# Sheet1.net
KiCad netlist of a schematic drawn in Altium Designer
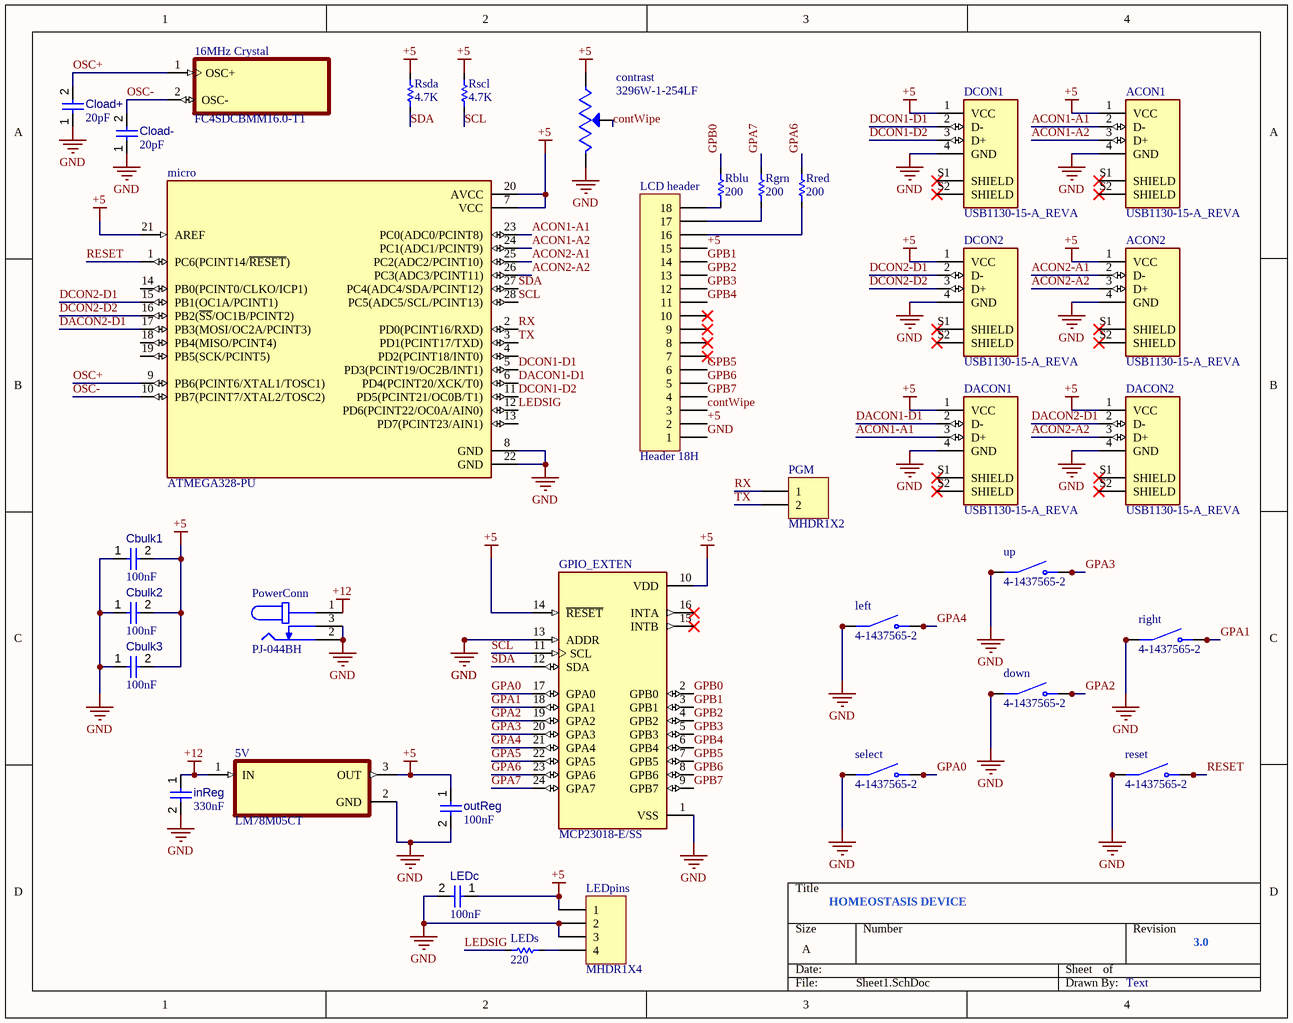
[diagram p0: Sheet1.SchDoc]

(export (version "E")
  (design (tool "Eeschema 10.0.6"))
  (components
    (comp (ref "5V")
      (value "LM78M05CT")
      (footprint "TO254P1054X470X1955-3")
      (description "Linear Voltage Regulator IC 1 Output 500mA TO-220-3")
      (fields (field (name "MF") "ON Semiconductor"))
      (libsource (lib "LM78M05CT") (part "LM78M05CT"))
    )
    (comp (ref "16MHz Crystal")
      (value "FC4SDCBMM16.0-T1")
      (footprint "XTAL_FOXSDLF/160-20")
      (description "16 MHz Â±30ppm Crystal 20pF 40 Ohms HC-49/US")
      (fields (field (name "MF") "Fox Electronics"))
      (libsource (lib "FC4SDCBMM16.0-T1") (part "FC4SDCBMM16.0-T1"))
    )
    (comp (ref "ACON1")
      (value "USB1130-15-A_REVA")
      (footprint "GCT_USB1130-15-A_REVA")
      (fields (field (name "MF") "{'manufacturer': u'Global Connector Technology'}"))
      (libsource (lib "SnapEDA_Library") (part "USB1130-15-A_REVA"))
    )
    (comp (ref "ACON2")
      (value "USB1130-15-A_REVA")
      (footprint "GCT_USB1130-15-A_REVA")
      (fields (field (name "MF") "{'manufacturer': u'Global Connector Technology'}"))
      (libsource (lib "SnapEDA_Library") (part "USB1130-15-A_REVA"))
    )
    (comp (ref "Cbulk1")
      (value "100nF")
      (footprint "CAPC0805(2012)145_L")
      (description "Chip Capacitor, 4.7µF +/-40%, 25V, 0805, Thickness 1.45 mm")
      (fields (field (name "TOLERANCE") "20%") (field (name "Comment") "Capacitor 4.7µF +/-40% 25V 0805"))
      (libsource (lib "University of Minnesota - Solar Vehicle Project") (part "CAP-NP-2"))
    )
    (comp (ref "Cbulk2")
      (value "100nF")
      (footprint "CAPC0805(2012)145_L")
      (description "Chip Capacitor, 4.7µF +/-40%, 25V, 0805, Thickness 1.45 mm")
      (fields (field (name "TOLERANCE") "20%") (field (name "Comment") "Capacitor 4.7µF +/-40% 25V 0805"))
      (libsource (lib "University of Minnesota - Solar Vehicle Project") (part "CAP-NP-2"))
    )
    (comp (ref "Cbulk3")
      (value "100nF")
      (footprint "CAPC0805(2012)145_L")
      (description "Chip Capacitor, 4.7µF +/-40%, 25V, 0805, Thickness 1.45 mm")
      (fields (field (name "TOLERANCE") "20%") (field (name "Comment") "Capacitor 4.7µF +/-40% 25V 0805"))
      (libsource (lib "University of Minnesota - Solar Vehicle Project") (part "CAP-NP-2"))
    )
    (comp (ref "Cload+")
      (value "20pF")
      (footprint "CAPC2013X135X45ML10T25")
      (description "Chip Capacitor, 1 uF, +/- 10%, 50 V, 0805 (2012 Metric)")
      (fields (field (name "TOLERANCE") "10%") (field (name "Comment") "Capacitor 1 uF +/- 10% 50 V 0805"))
      (libsource (lib "University of Minnesota - Solar Vehicle Project") (part "CAP-NP-2"))
    )
    (comp (ref "Cload-")
      (value "20pF")
      (footprint "CAPC2013X135X45ML10T25")
      (description "Chip Capacitor, 1 uF, +/- 10%, 50 V, 0805 (2012 Metric)")
      (fields (field (name "TOLERANCE") "10%") (field (name "Comment") "Capacitor 1 uF +/- 10% 50 V 0805"))
      (libsource (lib "University of Minnesota - Solar Vehicle Project") (part "CAP-NP-2"))
    )
    (comp (ref "contrast")
      (value "3296W-1-254LF")
      (footprint "TRIM_3296W-1-254LF")
      (fields (field (name "MF") "{'manufacturer': u'Bourns'}"))
      (libsource (lib "SnapEDA_Library") (part "3296W-1-254LF"))
    )
    (comp (ref "DACON1")
      (value "USB1130-15-A_REVA")
      (footprint "GCT_USB1130-15-A_REVA")
      (fields (field (name "MF") "{'manufacturer': u'Global Connector Technology'}"))
      (libsource (lib "SnapEDA_Library") (part "USB1130-15-A_REVA"))
    )
    (comp (ref "DACON2")
      (value "USB1130-15-A_REVA")
      (footprint "GCT_USB1130-15-A_REVA")
      (fields (field (name "MF") "{'manufacturer': u'Global Connector Technology'}"))
      (libsource (lib "SnapEDA_Library") (part "USB1130-15-A_REVA"))
    )
    (comp (ref "DCON1")
      (value "USB1130-15-A_REVA")
      (footprint "GCT_USB1130-15-A_REVA")
      (fields (field (name "MF") "{'manufacturer': u'Global Connector Technology'}"))
      (libsource (lib "SnapEDA_Library") (part "USB1130-15-A_REVA"))
    )
    (comp (ref "DCON2")
      (value "USB1130-15-A_REVA")
      (footprint "GCT_USB1130-15-A_REVA")
      (fields (field (name "MF") "{'manufacturer': u'Global Connector Technology'}"))
      (libsource (lib "SnapEDA_Library") (part "USB1130-15-A_REVA"))
    )
    (comp (ref "down")
      (value "4-1437565-2")
      (footprint "SW_4-1437565-2")
      (fields (field (name "MF") "{'manufacturer': u'TE Connectivity'}"))
      (libsource (lib "SnapEDA_Library") (part "4-1437565-2"))
    )
    (comp (ref "GPIO_EXTEN")
      (value "MCP23018-E/SS")
      (footprint "SOP65P780X200-24N")
      (description "IC: expander; 16bit I/O port; I2C; SSOP24; 1.8Ã·5.5VDC")
      (fields (field (name "MF") "{'manufacturer': u'Microchip'}"))
      (libsource (lib "SnapEDA_Library") (part "MCP23018-E/SS"))
    )
    (comp (ref "inReg")
      (value "330nF")
      (footprint "CAPC0805(2012)145_L")
      (description "Chip Capacitor, 4.7µF +/-40%, 25V, 0805, Thickness 1.45 mm")
      (fields (field (name "TOLERANCE") "20%") (field (name "Comment") "Capacitor 4.7µF +/-40% 25V 0805"))
      (libsource (lib "University of Minnesota - Solar Vehicle Project") (part "CAP-NP-2"))
    )
    (comp (ref "LCD header")
      (value "Header 18H")
      (footprint "HDR1X18H")
      (description "Header, 18-Pin, Right Angle")
      (fields (field (name "PUBLISHER") "Altium Limited"))
      (libsource (lib "Miscellaneous Connectors") (part "Header 18H"))
    )
    (comp (ref "LEDc")
      (value "100nF")
      (footprint "CAPC0805(2012)145_L")
      (description "Chip Capacitor, 4.7µF +/-40%, 25V, 0805, Thickness 1.45 mm")
      (fields (field (name "TOLERANCE") "20%") (field (name "Comment") "Capacitor 4.7µF +/-40% 25V 0805"))
      (libsource (lib "University of Minnesota - Solar Vehicle Project") (part "CAP-NP-2"))
    )
    (comp (ref "LEDpins")
      (value "MHDR1X4")
      (footprint "MHDR1X4")
      (description "Header, 4-Pin")
      (fields (field (name "PUBLISHER") "Altium Limited"))
      (libsource (lib "Miscellaneous Connectors") (part "MHDR1X4"))
    )
    (comp (ref "LEDs")
      (value "220")
      (footprint "0805_Resistor")
      (description "RES 4.7K OHM 1/8W 1% 0805 SMD")
      (fields
        (field (name "MANUFACTURER") "Yageo")
        (field (name "MANUFACTURER PART NUMBER") "AC0805FR-074K7L")
        (field (name "SVP CREATOR") "Andrew Wu")
      )
      (libsource (lib "University of Minnesota - Solar Vehicle Project") (part "Symbol"))
    )
    (comp (ref "left")
      (value "4-1437565-2")
      (footprint "SW_4-1437565-2")
      (fields (field (name "MF") "{'manufacturer': u'TE Connectivity'}"))
      (libsource (lib "SnapEDA_Library") (part "4-1437565-2"))
    )
    (comp (ref "micro")
      (value "ATMEGA328-PU")
      (footprint "DIP787W46P254L3467H508Q28")
      (description "AVR AVRÂ® ATmega Microcontroller IC 8-Bit 20MHz 32KB (16K x 16) FLASH 28-PDIP")
      (fields (field (name "MF") "{'manufacturer': u'Microchip Technology'}"))
      (libsource (lib "SnapEDA_Library") (part "ATMEGA328-PU"))
    )
    (comp (ref "outReg")
      (value "100nF")
      (footprint "CAPC0805(2012)145_L")
      (description "Chip Capacitor, 4.7µF +/-40%, 25V, 0805, Thickness 1.45 mm")
      (fields (field (name "TOLERANCE") "20%") (field (name "Comment") "Capacitor 4.7µF +/-40% 25V 0805"))
      (libsource (lib "University of Minnesota - Solar Vehicle Project") (part "CAP-NP-2"))
    )
    (comp (ref "PGM")
      (value "MHDR1X2")
      (footprint "MHDR1X2")
      (description "Header, 2-Pin")
      (fields (field (name "PUBLISHER") "Altium Limited"))
      (libsource (lib "Miscellaneous Connectors") (part "MHDR1X2"))
    )
    (comp (ref "PowerConn")
      (value "PJ-044BH")
      (footprint "CUI_PJ-044BH")
      (description "2.5 mm Center Pin, 5.0 A, Vertical, Through Hole, Dc Power Jack Connector")
      (fields (field (name "MF") "{'manufacturer': u'CUI Devices'}"))
      (libsource (lib "SnapEDA_Library") (part "PJ-044BH"))
    )
    (comp (ref "Rblu")
      (value "200")
      (footprint "0805_Resistor")
      (description "RES 200 OHM 1/8W 1% 0805 SMD")
      (fields
        (field (name "MANUFACTURER") "Yageo")
        (field (name "MANUFACTURER PART NUMBER") "RC0805FR-07200RL")
        (field (name "SVP CREATOR") "Spencer Berglund")
      )
      (libsource (lib "University of Minnesota - Solar Vehicle Project") (part "Symbol"))
    )
    (comp (ref "reset")
      (value "4-1437565-2")
      (footprint "SW_4-1437565-2")
      (fields (field (name "MF") "{'manufacturer': u'TE Connectivity'}"))
      (libsource (lib "SnapEDA_Library") (part "4-1437565-2"))
    )
    (comp (ref "Rgrn")
      (value "200")
      (footprint "0805_Resistor")
      (description "RES 200 OHM 1/8W 1% 0805 SMD")
      (fields
        (field (name "MANUFACTURER") "Yageo")
        (field (name "MANUFACTURER PART NUMBER") "RC0805FR-07200RL")
        (field (name "SVP CREATOR") "Spencer Berglund")
      )
      (libsource (lib "University of Minnesota - Solar Vehicle Project") (part "Symbol"))
    )
    (comp (ref "right")
      (value "4-1437565-2")
      (footprint "SW_4-1437565-2")
      (fields (field (name "MF") "{'manufacturer': u'TE Connectivity'}"))
      (libsource (lib "SnapEDA_Library") (part "4-1437565-2"))
    )
    (comp (ref "Rred")
      (value "200")
      (footprint "0805_Resistor")
      (description "RES 200 OHM 1/8W 1% 0805 SMD")
      (fields
        (field (name "MANUFACTURER") "Yageo")
        (field (name "MANUFACTURER PART NUMBER") "RC0805FR-07200RL")
        (field (name "SVP CREATOR") "Spencer Berglund")
      )
      (libsource (lib "University of Minnesota - Solar Vehicle Project") (part "Symbol"))
    )
    (comp (ref "Rscl")
      (value "4.7K")
      (footprint "0805_Resistor")
      (description "RES 4.7K OHM 1/8W 1% 0805 SMD")
      (fields
        (field (name "MANUFACTURER") "Yageo")
        (field (name "MANUFACTURER PART NUMBER") "AC0805FR-074K7L")
        (field (name "SVP CREATOR") "Andrew Wu")
      )
      (libsource (lib "University of Minnesota - Solar Vehicle Project") (part "Symbol"))
    )
    (comp (ref "Rsda")
      (value "4.7K")
      (footprint "0805_Resistor")
      (description "RES 4.7K OHM 1/8W 1% 0805 SMD")
      (fields
        (field (name "MANUFACTURER") "Yageo")
        (field (name "MANUFACTURER PART NUMBER") "AC0805FR-074K7L")
        (field (name "SVP CREATOR") "Andrew Wu")
      )
      (libsource (lib "University of Minnesota - Solar Vehicle Project") (part "Symbol"))
    )
    (comp (ref "select")
      (value "4-1437565-2")
      (footprint "SW_4-1437565-2")
      (fields (field (name "MF") "{'manufacturer': u'TE Connectivity'}"))
      (libsource (lib "SnapEDA_Library") (part "4-1437565-2"))
    )
    (comp (ref "up")
      (value "4-1437565-2")
      (footprint "SW_4-1437565-2")
      (fields (field (name "MF") "{'manufacturer': u'TE Connectivity'}"))
      (libsource (lib "SnapEDA_Library") (part "4-1437565-2"))
    )
  )
  (nets
    (net (code "1") (name "+5") (class "Default")
      (node (ref "5V") (pin "3") (pinfunction "OUT_3") (pintype "output"))
      (node (ref "ACON1") (pin "1") (pinfunction "VCC_1") (pintype "power_in"))
      (node (ref "ACON2") (pin "1") (pinfunction "VCC_1") (pintype "power_in"))
      (node (ref "Cbulk1") (pin "2") (pinfunction "2_2") (pintype "passive"))
      (node (ref "Cbulk2") (pin "2") (pinfunction "2_2") (pintype "passive"))
      (node (ref "Cbulk3") (pin "2") (pinfunction "2_2") (pintype "passive"))
      (node (ref "DACON1") (pin "1") (pinfunction "VCC_1") (pintype "power_in"))
      (node (ref "DACON2") (pin "1") (pinfunction "VCC_1") (pintype "power_in"))
      (node (ref "DCON1") (pin "1") (pinfunction "VCC_1") (pintype "power_in"))
      (node (ref "DCON2") (pin "1") (pinfunction "VCC_1") (pintype "power_in"))
      (node (ref "GPIO_EXTEN") (pin "10") (pinfunction "VDD_10") (pintype "power_in"))
      (node (ref "GPIO_EXTEN") (pin "14") (pinfunction "~{RESET}_14") (pintype "input"))
      (node (ref "LCD header") (pin "15") (pinfunction "15_15") (pintype "passive"))
      (node (ref "LCD header") (pin "2") (pinfunction "2_2") (pintype "passive"))
      (node (ref "LEDc") (pin "1") (pinfunction "1_1") (pintype "passive"))
      (node (ref "LEDpins") (pin "1") (pinfunction "1_1") (pintype "passive"))
      (node (ref "Rscl") (pin "1") (pinfunction "1_1") (pintype "passive"))
      (node (ref "Rsda") (pin "1") (pinfunction "1_1") (pintype "passive"))
      (node (ref "contrast") (pin "1") (pinfunction "CCW_1") (pintype "passive"))
      (node (ref "micro") (pin "20") (pinfunction "AVCC_20") (pintype "power_in"))
      (node (ref "micro") (pin "21") (pinfunction "AREF_21") (pintype "input"))
      (node (ref "micro") (pin "7") (pinfunction "VCC_7") (pintype "power_in"))
      (node (ref "outReg") (pin "1") (pinfunction "1_1") (pintype "passive"))
    )
    (net (code "2") (name "+12") (class "Default")
      (node (ref "5V") (pin "1") (pinfunction "IN_1") (pintype "input"))
      (node (ref "PowerConn") (pin "1") (pinfunction "1_1") (pintype "passive"))
      (node (ref "inReg") (pin "1") (pinfunction "1_1") (pintype "passive"))
    )
    (net (code "3") (name "/ACON1-A1") (class "Default")
      (node (ref "ACON1") (pin "2") (pinfunction "D-_2") (pintype "bidirectional"))
      (node (ref "DACON1") (pin "3") (pinfunction "D+_3") (pintype "bidirectional"))
      (node (ref "micro") (pin "23") (pinfunction "PC0(ADC0/PCINT8)_23") (pintype "bidirectional"))
    )
    (net (code "4") (name "/ACON1-A2") (class "Default")
      (node (ref "ACON1") (pin "3") (pinfunction "D+_3") (pintype "bidirectional"))
      (node (ref "micro") (pin "24") (pinfunction "PC1(ADC1/PCINT9)_24") (pintype "bidirectional"))
    )
    (net (code "5") (name "/ACON2-A1") (class "Default")
      (node (ref "ACON2") (pin "2") (pinfunction "D-_2") (pintype "bidirectional"))
      (node (ref "micro") (pin "25") (pinfunction "PC2(ADC2/PCINT10)_25") (pintype "bidirectional"))
    )
    (net (code "6") (name "/ACON2-A2") (class "Default")
      (node (ref "ACON2") (pin "3") (pinfunction "D+_3") (pintype "bidirectional"))
      (node (ref "DACON2") (pin "3") (pinfunction "D+_3") (pintype "bidirectional"))
      (node (ref "micro") (pin "26") (pinfunction "PC3(ADC3/PCINT11)_26") (pintype "bidirectional"))
    )
    (net (code "7") (name "/DACON1-D1") (class "Default")
      (node (ref "DACON1") (pin "2") (pinfunction "D-_2") (pintype "bidirectional"))
      (node (ref "micro") (pin "6") (pinfunction "PD4(PCINT20/XCK/T0)_6") (pintype "bidirectional"))
    )
    (net (code "8") (name "/DACON2-D1") (class "Default")
      (node (ref "DACON2") (pin "2") (pinfunction "D-_2") (pintype "bidirectional"))
      (node (ref "micro") (pin "17") (pinfunction "PB3(MOSI/OC2A/PCINT3)_17") (pintype "bidirectional"))
    )
    (net (code "9") (name "/DCON1-D1") (class "Default")
      (node (ref "DCON1") (pin "2") (pinfunction "D-_2") (pintype "bidirectional"))
      (node (ref "micro") (pin "5") (pinfunction "PD3(PCINT19/OC2B/INT1)_5") (pintype "bidirectional"))
    )
    (net (code "10") (name "/DCON1-D2") (class "Default")
      (node (ref "DCON1") (pin "3") (pinfunction "D+_3") (pintype "bidirectional"))
      (node (ref "micro") (pin "11") (pinfunction "PD5(PCINT21/OC0B/T1)_11") (pintype "bidirectional"))
    )
    (net (code "11") (name "/DCON2-D1") (class "Default")
      (node (ref "DCON2") (pin "2") (pinfunction "D-_2") (pintype "bidirectional"))
      (node (ref "micro") (pin "15") (pinfunction "PB1(OC1A/PCINT1)_15") (pintype "bidirectional"))
    )
    (net (code "12") (name "/DCON2-D2") (class "Default")
      (node (ref "DCON2") (pin "3") (pinfunction "D+_3") (pintype "bidirectional"))
      (node (ref "micro") (pin "16") (pinfunction "PB2(~{SS}/OC1B/PCINT2)_16") (pintype "bidirectional"))
    )
    (net (code "13") (name "/GPA0") (class "Default")
      (node (ref "GPIO_EXTEN") (pin "17") (pinfunction "GPA0_17") (pintype "bidirectional"))
      (node (ref "select") (pin "3") (pinfunction "NO_3") (pintype "passive"))
      (node (ref "select") (pin "4") (pinfunction "NO_4") (pintype "passive"))
    )
    (net (code "14") (name "/GPA1") (class "Default")
      (node (ref "GPIO_EXTEN") (pin "18") (pinfunction "GPA1_18") (pintype "bidirectional"))
      (node (ref "right") (pin "3") (pinfunction "NO_3") (pintype "passive"))
      (node (ref "right") (pin "4") (pinfunction "NO_4") (pintype "passive"))
    )
    (net (code "15") (name "/GPA2") (class "Default")
      (node (ref "GPIO_EXTEN") (pin "19") (pinfunction "GPA2_19") (pintype "bidirectional"))
      (node (ref "down") (pin "3") (pinfunction "NO_3") (pintype "passive"))
      (node (ref "down") (pin "4") (pinfunction "NO_4") (pintype "passive"))
    )
    (net (code "16") (name "/GPA3") (class "Default")
      (node (ref "GPIO_EXTEN") (pin "20") (pinfunction "GPA3_20") (pintype "bidirectional"))
      (node (ref "up") (pin "3") (pinfunction "NO_3") (pintype "passive"))
      (node (ref "up") (pin "4") (pinfunction "NO_4") (pintype "passive"))
    )
    (net (code "17") (name "/GPA4") (class "Default")
      (node (ref "GPIO_EXTEN") (pin "21") (pinfunction "GPA4_21") (pintype "bidirectional"))
      (node (ref "left") (pin "3") (pinfunction "NO_3") (pintype "passive"))
      (node (ref "left") (pin "4") (pinfunction "NO_4") (pintype "passive"))
    )
    (net (code "18") (name "/GPA5") (class "Default")
      (node (ref "GPIO_EXTEN") (pin "22") (pinfunction "GPA5_22") (pintype "bidirectional"))
    )
    (net (code "19") (name "/GPA6") (class "Default")
      (node (ref "GPIO_EXTEN") (pin "23") (pinfunction "GPA6_23") (pintype "bidirectional"))
      (node (ref "Rred") (pin "2") (pinfunction "2_2") (pintype "passive"))
    )
    (net (code "20") (name "/GPA7") (class "Default")
      (node (ref "GPIO_EXTEN") (pin "24") (pinfunction "GPA7_24") (pintype "bidirectional"))
      (node (ref "Rgrn") (pin "2") (pinfunction "2_2") (pintype "passive"))
    )
    (net (code "21") (name "/GPB0") (class "Default")
      (node (ref "GPIO_EXTEN") (pin "2") (pinfunction "GPB0_2") (pintype "bidirectional"))
      (node (ref "Rblu") (pin "2") (pinfunction "2_2") (pintype "passive"))
    )
    (net (code "22") (name "/GPB1") (class "Default")
      (node (ref "GPIO_EXTEN") (pin "3") (pinfunction "GPB1_3") (pintype "bidirectional"))
      (node (ref "LCD header") (pin "14") (pinfunction "14_14") (pintype "passive"))
    )
    (net (code "23") (name "/GPB2") (class "Default")
      (node (ref "GPIO_EXTEN") (pin "4") (pinfunction "GPB2_4") (pintype "bidirectional"))
      (node (ref "LCD header") (pin "13") (pinfunction "13_13") (pintype "passive"))
    )
    (net (code "24") (name "/GPB3") (class "Default")
      (node (ref "GPIO_EXTEN") (pin "5") (pinfunction "GPB3_5") (pintype "bidirectional"))
      (node (ref "LCD header") (pin "12") (pinfunction "12_12") (pintype "passive"))
    )
    (net (code "25") (name "/GPB4") (class "Default")
      (node (ref "GPIO_EXTEN") (pin "6") (pinfunction "GPB4_6") (pintype "bidirectional"))
      (node (ref "LCD header") (pin "11") (pinfunction "11_11") (pintype "passive"))
    )
    (net (code "26") (name "/GPB5") (class "Default")
      (node (ref "GPIO_EXTEN") (pin "7") (pinfunction "GPB5_7") (pintype "bidirectional"))
      (node (ref "LCD header") (pin "6") (pinfunction "6_6") (pintype "passive"))
    )
    (net (code "27") (name "/GPB6") (class "Default")
      (node (ref "GPIO_EXTEN") (pin "8") (pinfunction "GPB6_8") (pintype "bidirectional"))
      (node (ref "LCD header") (pin "5") (pinfunction "5_5") (pintype "passive"))
    )
    (net (code "28") (name "/GPB7") (class "Default")
      (node (ref "GPIO_EXTEN") (pin "9") (pinfunction "GPB7_9") (pintype "bidirectional"))
      (node (ref "LCD header") (pin "4") (pinfunction "4_4") (pintype "passive"))
    )
    (net (code "29") (name "/LEDSIG") (class "Default")
      (node (ref "LEDs") (pin "1") (pinfunction "1_1") (pintype "passive"))
      (node (ref "micro") (pin "12") (pinfunction "PD6(PCINT22/OC0A/AIN0)_12") (pintype "bidirectional"))
    )
    (net (code "30") (name "/OSC+") (class "Default")
      (node (ref "16MHz Crystal") (pin "1") (pinfunction "OSC+_1") (pintype "input"))
      (node (ref "Cload+") (pin "2") (pinfunction "2_2") (pintype "passive"))
      (node (ref "micro") (pin "9") (pinfunction "PB6(PCINT6/XTAL1/TOSC1)_9") (pintype "bidirectional"))
    )
    (net (code "31") (name "/OSC-") (class "Default")
      (node (ref "16MHz Crystal") (pin "2") (pinfunction "OSC-_2") (pintype "bidirectional"))
      (node (ref "Cload-") (pin "2") (pinfunction "2_2") (pintype "passive"))
      (node (ref "micro") (pin "10") (pinfunction "PB7(PCINT7/XTAL2/TOSC2)_10") (pintype "bidirectional"))
    )
    (net (code "32") (name "/RESET") (class "Default")
      (node (ref "micro") (pin "1") (pinfunction "PC6(PCINT14/~{RESET})_1") (pintype "bidirectional"))
      (node (ref "reset") (pin "3") (pinfunction "NO_3") (pintype "passive"))
      (node (ref "reset") (pin "4") (pinfunction "NO_4") (pintype "passive"))
    )
    (net (code "33") (name "/RX") (class "Default")
      (node (ref "PGM") (pin "1") (pinfunction "1_1") (pintype "passive"))
      (node (ref "micro") (pin "2") (pinfunction "PD0(PCINT16/RXD)_2") (pintype "bidirectional"))
    )
    (net (code "34") (name "/SCL") (class "Default")
      (node (ref "GPIO_EXTEN") (pin "11") (pinfunction "SCL_11") (pintype "input"))
      (node (ref "Rscl") (pin "2") (pinfunction "2_2") (pintype "passive"))
      (node (ref "micro") (pin "28") (pinfunction "PC5(ADC5/SCL/PCINT13)_28") (pintype "bidirectional"))
    )
    (net (code "35") (name "/SDA") (class "Default")
      (node (ref "GPIO_EXTEN") (pin "12") (pinfunction "SDA_12") (pintype "bidirectional"))
      (node (ref "Rsda") (pin "2") (pinfunction "2_2") (pintype "passive"))
      (node (ref "micro") (pin "27") (pinfunction "PC4(ADC4/SDA/PCINT12)_27") (pintype "bidirectional"))
    )
    (net (code "36") (name "/TX") (class "Default")
      (node (ref "PGM") (pin "2") (pinfunction "2_2") (pintype "passive"))
      (node (ref "micro") (pin "3") (pinfunction "PD1(PCINT17/TXD)_3") (pintype "bidirectional"))
    )
    (net (code "37") (name "/contWipe") (class "Default")
      (node (ref "LCD header") (pin "3") (pinfunction "3_3") (pintype "passive"))
      (node (ref "contrast") (pin "2") (pinfunction "WIPER_2") (pintype "passive"))
    )
    (net (code "38") (name "GND") (class "Default")
      (node (ref "5V") (pin "2") (pinfunction "GND_2") (pintype "power_in"))
      (node (ref "ACON1") (pin "4") (pinfunction "GND_4") (pintype "power_in"))
      (node (ref "ACON2") (pin "4") (pinfunction "GND_4") (pintype "power_in"))
      (node (ref "Cbulk1") (pin "1") (pinfunction "1_1") (pintype "passive"))
      (node (ref "Cbulk2") (pin "1") (pinfunction "1_1") (pintype "passive"))
      (node (ref "Cbulk3") (pin "1") (pinfunction "1_1") (pintype "passive"))
      (node (ref "Cload+") (pin "1") (pinfunction "1_1") (pintype "passive"))
      (node (ref "Cload-") (pin "1") (pinfunction "1_1") (pintype "passive"))
      (node (ref "DACON1") (pin "4") (pinfunction "GND_4") (pintype "power_in"))
      (node (ref "DACON2") (pin "4") (pinfunction "GND_4") (pintype "power_in"))
      (node (ref "DCON1") (pin "4") (pinfunction "GND_4") (pintype "power_in"))
      (node (ref "DCON2") (pin "4") (pinfunction "GND_4") (pintype "power_in"))
      (node (ref "GPIO_EXTEN") (pin "1") (pinfunction "VSS_1") (pintype "power_in"))
      (node (ref "GPIO_EXTEN") (pin "13") (pinfunction "ADDR_13") (pintype "input"))
      (node (ref "LCD header") (pin "1") (pinfunction "1_1") (pintype "passive"))
      (node (ref "LEDc") (pin "2") (pinfunction "2_2") (pintype "passive"))
      (node (ref "LEDpins") (pin "2") (pinfunction "2_2") (pintype "passive"))
      (node (ref "LEDpins") (pin "3") (pinfunction "3_3") (pintype "passive"))
      (node (ref "PowerConn") (pin "2") (pinfunction "2_2") (pintype "passive"))
      (node (ref "PowerConn") (pin "3") (pinfunction "3_3") (pintype "passive"))
      (node (ref "contrast") (pin "3") (pinfunction "CW_3") (pintype "passive"))
      (node (ref "down") (pin "1") (pinfunction "COM_1") (pintype "passive"))
      (node (ref "down") (pin "2") (pinfunction "COM_2") (pintype "passive"))
      (node (ref "inReg") (pin "2") (pinfunction "2_2") (pintype "passive"))
      (node (ref "left") (pin "1") (pinfunction "COM_1") (pintype "passive"))
      (node (ref "left") (pin "2") (pinfunction "COM_2") (pintype "passive"))
      (node (ref "micro") (pin "22") (pinfunction "GND_22") (pintype "power_in"))
      (node (ref "micro") (pin "8") (pinfunction "GND_8") (pintype "power_in"))
      (node (ref "outReg") (pin "2") (pinfunction "2_2") (pintype "passive"))
      (node (ref "reset") (pin "1") (pinfunction "COM_1") (pintype "passive"))
      (node (ref "reset") (pin "2") (pinfunction "COM_2") (pintype "passive"))
      (node (ref "right") (pin "1") (pinfunction "COM_1") (pintype "passive"))
      (node (ref "right") (pin "2") (pinfunction "COM_2") (pintype "passive"))
      (node (ref "select") (pin "1") (pinfunction "COM_1") (pintype "passive"))
      (node (ref "select") (pin "2") (pinfunction "COM_2") (pintype "passive"))
      (node (ref "up") (pin "1") (pinfunction "COM_1") (pintype "passive"))
      (node (ref "up") (pin "2") (pinfunction "COM_2") (pintype "passive"))
    )
    (net (code "39") (name "Net-(LCD header-Pad16)") (class "Default")
      (node (ref "LCD header") (pin "16") (pinfunction "16_16") (pintype "passive"))
      (node (ref "Rred") (pin "1") (pinfunction "1_1") (pintype "passive"))
    )
    (net (code "40") (name "Net-(LCD header-Pad17)") (class "Default")
      (node (ref "LCD header") (pin "17") (pinfunction "17_17") (pintype "passive"))
      (node (ref "Rgrn") (pin "1") (pinfunction "1_1") (pintype "passive"))
    )
    (net (code "41") (name "Net-(LCD header-Pad18)") (class "Default")
      (node (ref "LCD header") (pin "18") (pinfunction "18_18") (pintype "passive"))
      (node (ref "Rblu") (pin "1") (pinfunction "1_1") (pintype "passive"))
    )
    (net (code "42") (name "Net-(LEDpins-Pad4)") (class "Default")
      (node (ref "LEDpins") (pin "4") (pinfunction "4_4") (pintype "passive"))
      (node (ref "LEDs") (pin "2") (pinfunction "2_2") (pintype "passive"))
    )
    (net (code "43") (name "unconnected-(ACON1-SHIELD-PadS1)") (class "Default")
      (node (ref "ACON1") (pin "S1") (pinfunction "SHIELD_S1") (pintype "passive+no_connect"))
    )
    (net (code "44") (name "unconnected-(ACON1-SHIELD-PadS2)") (class "Default")
      (node (ref "ACON1") (pin "S2") (pinfunction "SHIELD_S2") (pintype "passive+no_connect"))
    )
    (net (code "45") (name "unconnected-(ACON2-SHIELD-PadS1)") (class "Default")
      (node (ref "ACON2") (pin "S1") (pinfunction "SHIELD_S1") (pintype "passive+no_connect"))
    )
    (net (code "46") (name "unconnected-(ACON2-SHIELD-PadS2)") (class "Default")
      (node (ref "ACON2") (pin "S2") (pinfunction "SHIELD_S2") (pintype "passive+no_connect"))
    )
    (net (code "47") (name "unconnected-(DACON1-SHIELD-PadS1)") (class "Default")
      (node (ref "DACON1") (pin "S1") (pinfunction "SHIELD_S1") (pintype "passive+no_connect"))
    )
    (net (code "48") (name "unconnected-(DACON1-SHIELD-PadS2)") (class "Default")
      (node (ref "DACON1") (pin "S2") (pinfunction "SHIELD_S2") (pintype "passive+no_connect"))
    )
    (net (code "49") (name "unconnected-(DACON2-SHIELD-PadS1)") (class "Default")
      (node (ref "DACON2") (pin "S1") (pinfunction "SHIELD_S1") (pintype "passive+no_connect"))
    )
    (net (code "50") (name "unconnected-(DACON2-SHIELD-PadS2)") (class "Default")
      (node (ref "DACON2") (pin "S2") (pinfunction "SHIELD_S2") (pintype "passive+no_connect"))
    )
    (net (code "51") (name "unconnected-(DCON1-SHIELD-PadS1)") (class "Default")
      (node (ref "DCON1") (pin "S1") (pinfunction "SHIELD_S1") (pintype "passive+no_connect"))
    )
    (net (code "52") (name "unconnected-(DCON1-SHIELD-PadS2)") (class "Default")
      (node (ref "DCON1") (pin "S2") (pinfunction "SHIELD_S2") (pintype "passive+no_connect"))
    )
    (net (code "53") (name "unconnected-(DCON2-SHIELD-PadS1)") (class "Default")
      (node (ref "DCON2") (pin "S1") (pinfunction "SHIELD_S1") (pintype "passive+no_connect"))
    )
    (net (code "54") (name "unconnected-(DCON2-SHIELD-PadS2)") (class "Default")
      (node (ref "DCON2") (pin "S2") (pinfunction "SHIELD_S2") (pintype "passive+no_connect"))
    )
    (net (code "55") (name "unconnected-(GPIO_EXTEN-INTA-Pad16)") (class "Default")
      (node (ref "GPIO_EXTEN") (pin "16") (pinfunction "INTA_16") (pintype "output+no_connect"))
    )
    (net (code "56") (name "unconnected-(GPIO_EXTEN-INTB-Pad15)") (class "Default")
      (node (ref "GPIO_EXTEN") (pin "15") (pinfunction "INTB_15") (pintype "output+no_connect"))
    )
    (net (code "57") (name "unconnected-(LCD header-Pad7)") (class "Default")
      (node (ref "LCD header") (pin "7") (pinfunction "7_7") (pintype "passive+no_connect"))
    )
    (net (code "58") (name "unconnected-(LCD header-Pad8)") (class "Default")
      (node (ref "LCD header") (pin "8") (pinfunction "8_8") (pintype "passive+no_connect"))
    )
    (net (code "59") (name "unconnected-(LCD header-Pad9)") (class "Default")
      (node (ref "LCD header") (pin "9") (pinfunction "9_9") (pintype "passive+no_connect"))
    )
    (net (code "60") (name "unconnected-(LCD header-Pad10)") (class "Default")
      (node (ref "LCD header") (pin "10") (pinfunction "10_10") (pintype "passive+no_connect"))
    )
    (net (code "61") (name "unconnected-(micro-PB0(PCINT0{slash}CLKO{slash}ICP1)-Pad14)") (class "Default")
      (node (ref "micro") (pin "14") (pinfunction "PB0(PCINT0/CLKO/ICP1)_14") (pintype "bidirectional"))
    )
    (net (code "62") (name "unconnected-(micro-PB4(MISO{slash}PCINT4)-Pad18)") (class "Default")
      (node (ref "micro") (pin "18") (pinfunction "PB4(MISO/PCINT4)_18") (pintype "bidirectional"))
    )
    (net (code "63") (name "unconnected-(micro-PB5(SCK{slash}PCINT5)-Pad19)") (class "Default")
      (node (ref "micro") (pin "19") (pinfunction "PB5(SCK/PCINT5)_19") (pintype "bidirectional"))
    )
    (net (code "64") (name "unconnected-(micro-PD2(PCINT18{slash}INT0)-Pad4)") (class "Default")
      (node (ref "micro") (pin "4") (pinfunction "PD2(PCINT18/INT0)_4") (pintype "bidirectional"))
    )
    (net (code "65") (name "unconnected-(micro-PD7(PCINT23{slash}AIN1)-Pad13)") (class "Default")
      (node (ref "micro") (pin "13") (pinfunction "PD7(PCINT23/AIN1)_13") (pintype "bidirectional"))
    )
  )
)
